# DisplayAddOn_V004.net
KiCad netlist of a schematic drawn in EAGLE
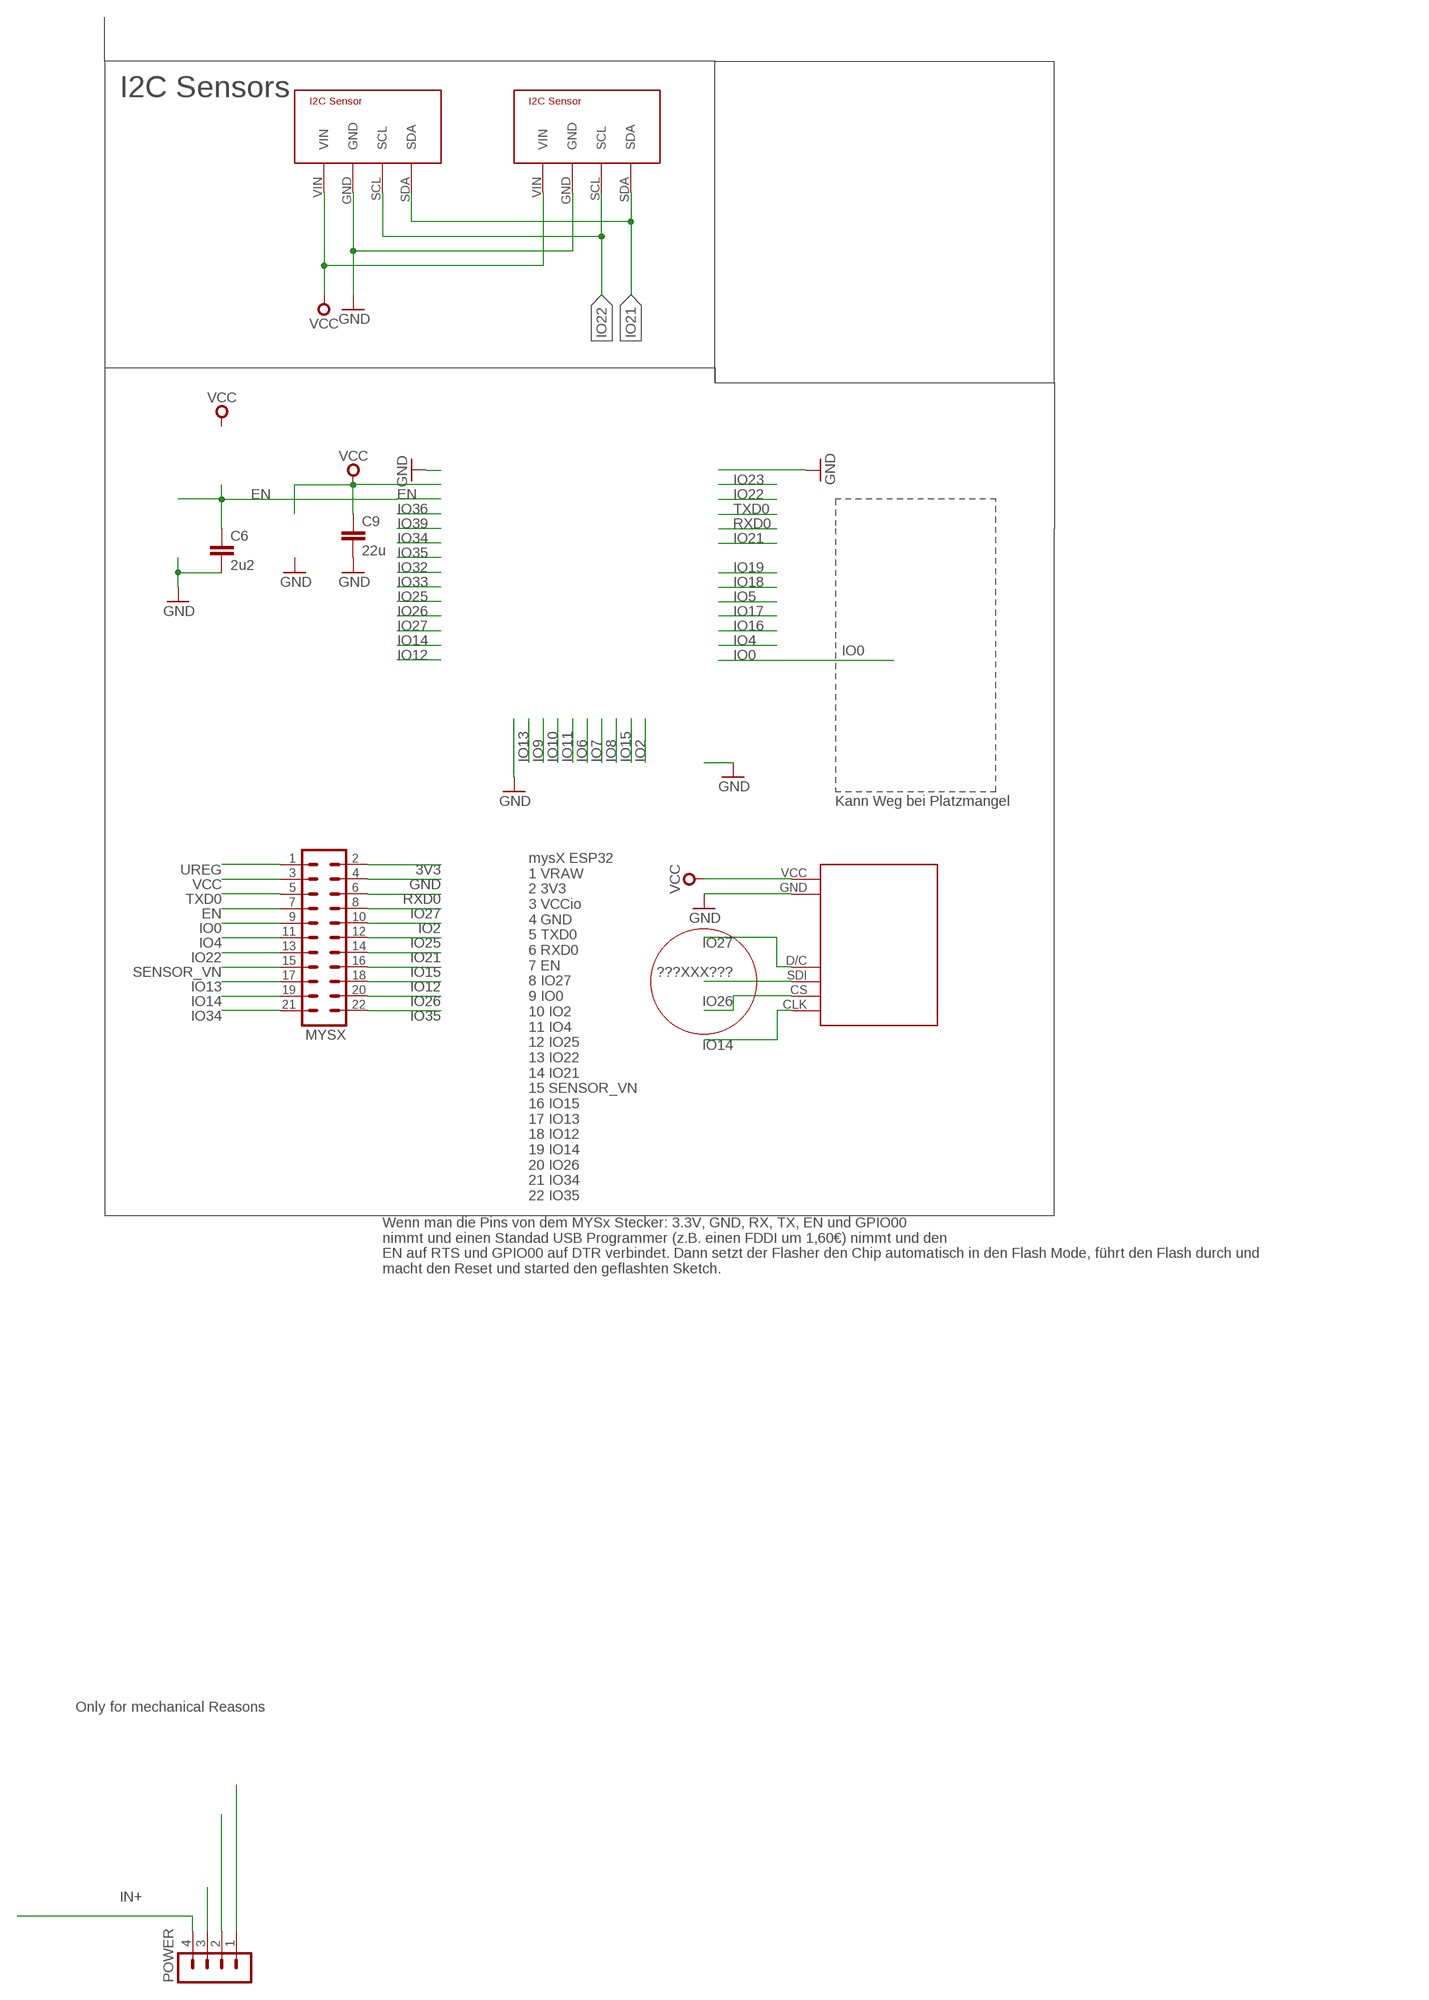
[diagram p0: schematic, sheet 1]

(export (version "E")
  (design (tool "Eeschema 10.0.6"))
  (components
    (comp (ref "C6")
      (value "2u2")
      (footprint "eagle-import:C0805")
      (libsource (lib "eagle-import") (part "C-EUC0805"))
    )
    (comp (ref "C9")
      (value "22u")
      (footprint "eagle-import:C0805")
      (libsource (lib "eagle-import") (part "C-EUC0805"))
    )
    (comp (ref "MYSX")
      (value "MA11-2")
      (footprint "eagle-import:MA11-2")
      (libsource (lib "eagle-import") (part "MA11-2"))
    )
    (comp (ref "POWER")
      (value "MA04-1")
      (footprint "eagle-import:MA04-1")
      (libsource (lib "eagle-import") (part "MA04-1"))
    )
    (comp (ref "U$1")
      (value "HELTEC_1.54STANDARD1")
      (footprint "eagle-import:HELTEC_1.54INCH")
      (libsource (lib "eagle-import") (part "HELTEC_1.54STANDARD1"))
    )
    (comp (ref "U$2")
      (value "I2C-BREAKOUT")
      (footprint "eagle-import:I2C_BREAKOUT")
      (libsource (lib "eagle-import") (part "I2C-BREAKOUT"))
    )
    (comp (ref "U$4")
      (value "I2C-BREAKOUT")
      (footprint "eagle-import:I2C_BREAKOUT")
      (libsource (lib "eagle-import") (part "I2C-BREAKOUT"))
    )
  )
  (nets
    (net (code "1") (name "/3V3") (class "Default")
      (node (ref "MYSX") (pin "2") (pinfunction "2_2") (pintype "passive"))
    )
    (net (code "2") (name "/???XXX???") (class "Default")
      (node (ref "U$1") (pin "SDI") (pinfunction "SDI_SDI") (pintype "bidirectional"))
    )
    (net (code "3") (name "/EN") (class "Default")
      (node (ref "C6") (pin "1") (pinfunction "1_1") (pintype "passive"))
      (node (ref "MYSX") (pin "7") (pinfunction "7_7") (pintype "passive"))
    )
    (net (code "4") (name "/IN+") (class "Default")
      (node (ref "POWER") (pin "4") (pinfunction "4_4") (pintype "passive"))
    )
    (net (code "5") (name "/IO0") (class "Default")
      (node (ref "MYSX") (pin "9") (pinfunction "9_9") (pintype "passive"))
    )
    (net (code "6") (name "/IO2") (class "Default")
      (node (ref "MYSX") (pin "10") (pinfunction "10_10") (pintype "passive"))
    )
    (net (code "7") (name "/IO4") (class "Default")
      (node (ref "MYSX") (pin "11") (pinfunction "11_11") (pintype "passive"))
    )
    (net (code "15") (name "/IO12") (class "Default")
      (node (ref "MYSX") (pin "18") (pinfunction "18_18") (pintype "passive"))
    )
    (net (code "16") (name "/IO13") (class "Default")
      (node (ref "MYSX") (pin "17") (pinfunction "17_17") (pintype "passive"))
    )
    (net (code "17") (name "/IO14") (class "Default")
      (node (ref "MYSX") (pin "19") (pinfunction "19_19") (pintype "passive"))
      (node (ref "U$1") (pin "CLK") (pinfunction "CLK_CLK") (pintype "bidirectional"))
    )
    (net (code "18") (name "/IO15") (class "Default")
      (node (ref "MYSX") (pin "16") (pinfunction "16_16") (pintype "passive"))
    )
    (net (code "24") (name "/IO25") (class "Default")
      (node (ref "MYSX") (pin "12") (pinfunction "12_12") (pintype "passive"))
    )
    (net (code "25") (name "/IO26") (class "Default")
      (node (ref "MYSX") (pin "20") (pinfunction "20_20") (pintype "passive"))
      (node (ref "U$1") (pin "CS") (pinfunction "CS_CS") (pintype "bidirectional"))
    )
    (net (code "26") (name "/IO27") (class "Default")
      (node (ref "MYSX") (pin "8") (pinfunction "8_8") (pintype "passive"))
      (node (ref "U$1") (pin "D/C") (pinfunction "D/C_D/C") (pintype "bidirectional"))
    )
    (net (code "29") (name "/IO34") (class "Default")
      (node (ref "MYSX") (pin "21") (pinfunction "21_21") (pintype "passive"))
    )
    (net (code "30") (name "/IO35") (class "Default")
      (node (ref "MYSX") (pin "22") (pinfunction "22_22") (pintype "passive"))
    )
    (net (code "33") (name "/RXD0") (class "Default")
      (node (ref "MYSX") (pin "6") (pinfunction "6_6") (pintype "passive"))
    )
    (net (code "34") (name "/SENSOR_VN") (class "Default")
      (node (ref "MYSX") (pin "15") (pinfunction "15_15") (pintype "passive"))
    )
    (net (code "35") (name "/TXD0") (class "Default")
      (node (ref "MYSX") (pin "5") (pinfunction "5_5") (pintype "passive"))
    )
    (net (code "36") (name "/UREG") (class "Default")
      (node (ref "MYSX") (pin "1") (pinfunction "1_1") (pintype "passive"))
    )
    (net (code "37") (name "GND") (class "Default")
      (node (ref "C6") (pin "2") (pinfunction "2_2") (pintype "passive"))
      (node (ref "C9") (pin "2") (pinfunction "2_2") (pintype "passive"))
      (node (ref "MYSX") (pin "4") (pinfunction "4_4") (pintype "passive"))
      (node (ref "U$1") (pin "GND") (pinfunction "GND_GND") (pintype "power_in"))
      (node (ref "U$2") (pin "GND") (pinfunction "GND_GND") (pintype "bidirectional"))
      (node (ref "U$4") (pin "GND") (pinfunction "GND_GND") (pintype "bidirectional"))
    )
    (net (code "38") (name "IO21") (class "Default")
      (node (ref "MYSX") (pin "14") (pinfunction "14_14") (pintype "passive"))
      (node (ref "U$2") (pin "SDA") (pinfunction "SDA_SDA") (pintype "bidirectional"))
      (node (ref "U$4") (pin "SDA") (pinfunction "SDA_SDA") (pintype "bidirectional"))
    )
    (net (code "39") (name "IO22") (class "Default")
      (node (ref "MYSX") (pin "13") (pinfunction "13_13") (pintype "passive"))
      (node (ref "U$2") (pin "SCL") (pinfunction "SCL_SCL") (pintype "bidirectional"))
      (node (ref "U$4") (pin "SCL") (pinfunction "SCL_SCL") (pintype "bidirectional"))
    )
    (net (code "40") (name "VCC") (class "Default")
      (node (ref "C9") (pin "1") (pinfunction "1_1") (pintype "passive"))
      (node (ref "MYSX") (pin "3") (pinfunction "3_3") (pintype "passive"))
      (node (ref "U$1") (pin "VCC") (pinfunction "VCC_VCC") (pintype "power_in"))
      (node (ref "U$2") (pin "VIN") (pinfunction "VIN_VIN") (pintype "bidirectional"))
      (node (ref "U$4") (pin "VIN") (pinfunction "VIN_VIN") (pintype "bidirectional"))
    )
    (net (code "41") (name "unconnected-(POWER-Pad1)") (class "Default")
      (node (ref "POWER") (pin "1") (pinfunction "1_1") (pintype "passive"))
    )
    (net (code "42") (name "unconnected-(POWER-Pad2)") (class "Default")
      (node (ref "POWER") (pin "2") (pinfunction "2_2") (pintype "passive"))
    )
    (net (code "43") (name "unconnected-(POWER-Pad3)") (class "Default")
      (node (ref "POWER") (pin "3") (pinfunction "3_3") (pintype "passive"))
    )
  )
)
